# io_shield.net
KiCad netlist of a schematic drawn in EAGLE
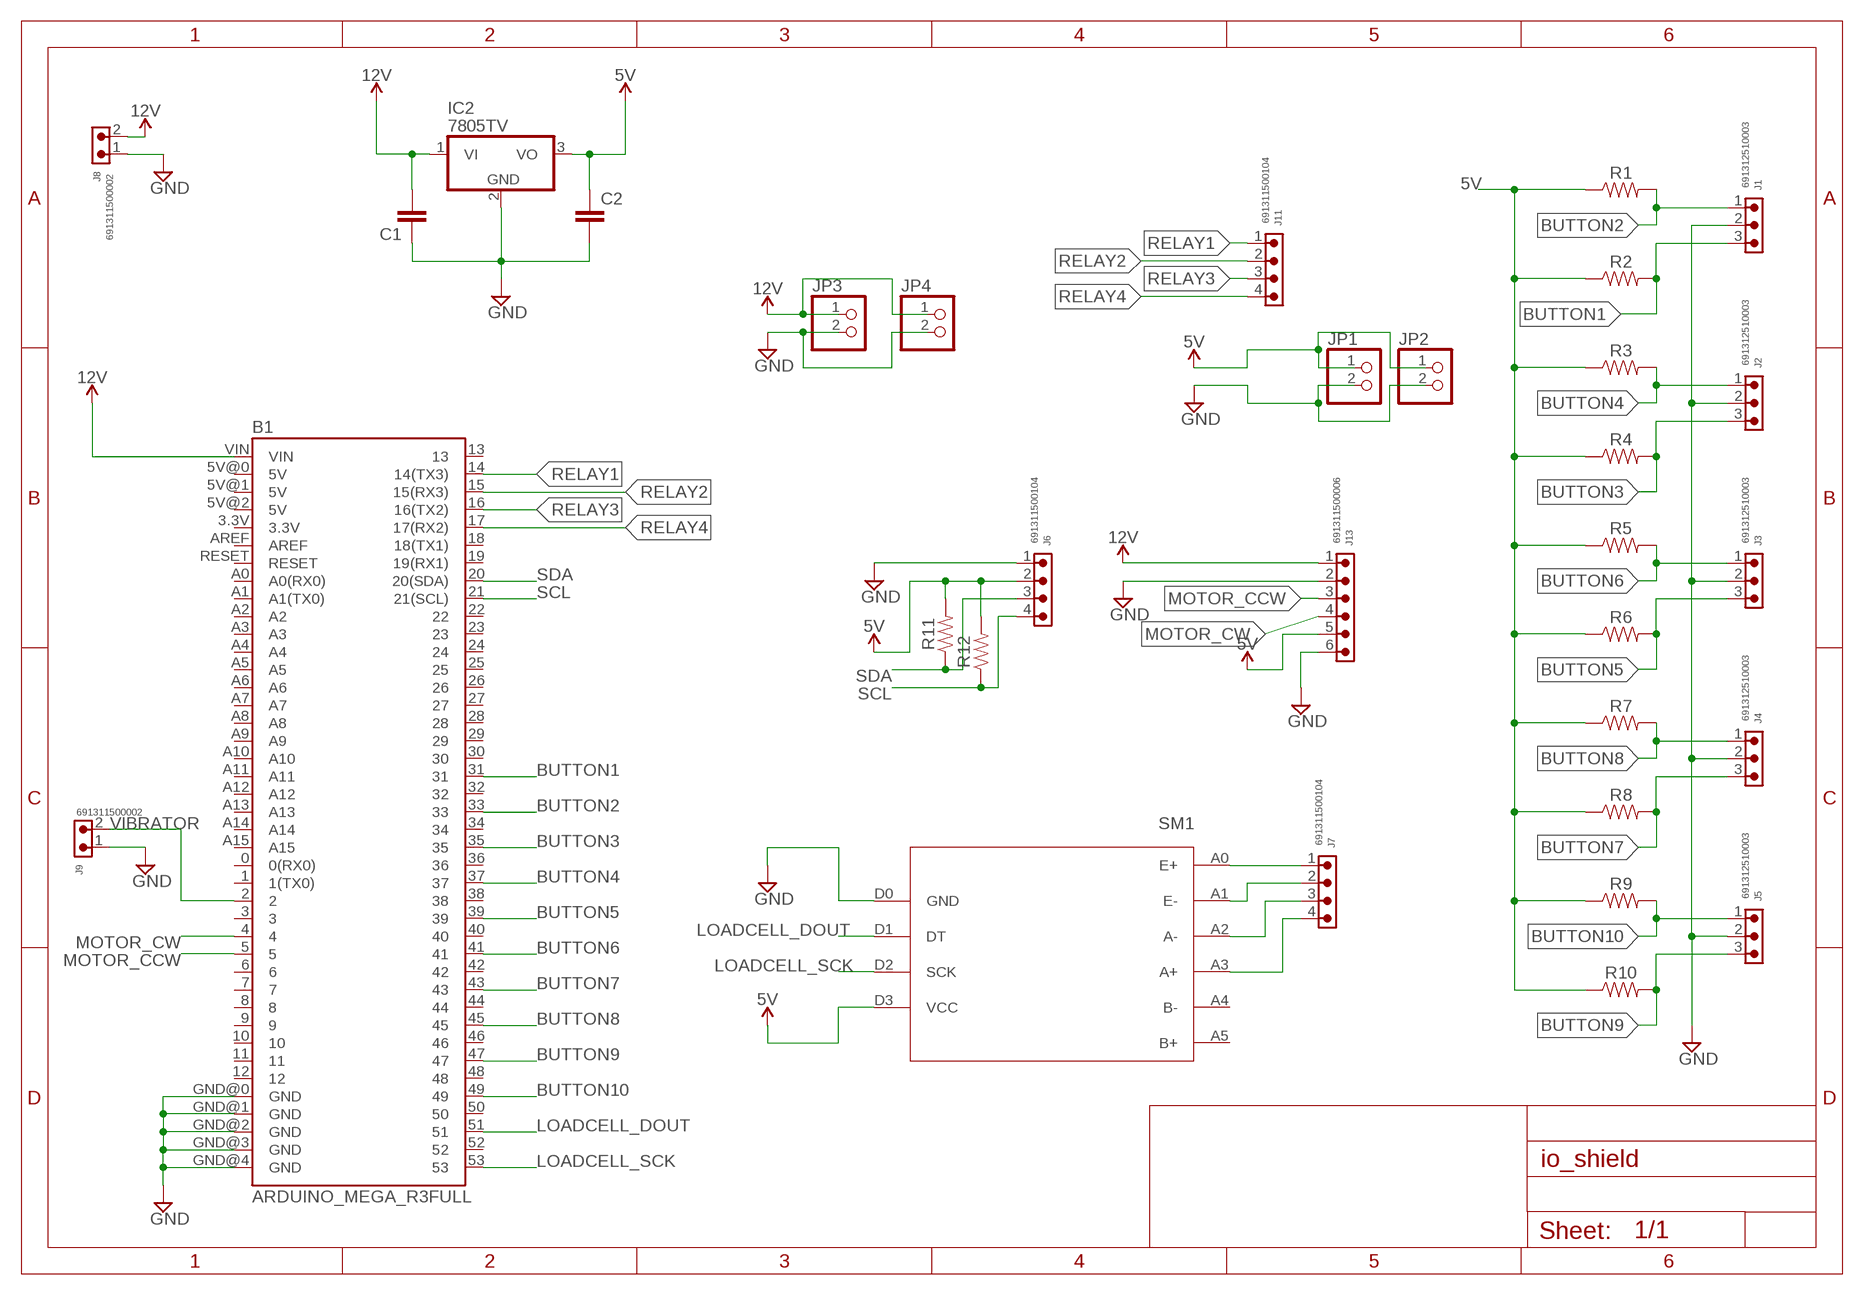
[diagram p0: schematic, sheet 1]

(export (version "E")
  (design (tool "Eeschema 10.0.6"))
  (components
    (comp (ref "B1")
      (value "ARDUINO_MEGA_R3FULL")
      (footprint "eagle-import:ARDUINO_MEGA")
      (libsource (lib "eagle-import") (part "ARDUINO_MEGA_R3FULL"))
    )
    (comp (ref "C1")
      (value "C-EU050-025X075")
      (footprint "eagle-import:C050-025X075")
      (libsource (lib "eagle-import") (part "C-EU050-025X075"))
    )
    (comp (ref "C2")
      (value "C-EU050-025X075")
      (footprint "eagle-import:C050-025X075")
      (libsource (lib "eagle-import") (part "C-EU050-025X075"))
    )
    (comp (ref "IC2")
      (value "7805TV")
      (footprint "eagle-import:TO220V")
      (libsource (lib "eagle-import") (part "78TV05"))
    )
    (comp (ref "J1")
      (value "691312510003")
      (footprint "eagle-import:691312510003")
      (libsource (lib "eagle-import") (part "691312510003"))
    )
    (comp (ref "J2")
      (value "691312510003")
      (footprint "eagle-import:691312510003")
      (libsource (lib "eagle-import") (part "691312510003"))
    )
    (comp (ref "J3")
      (value "691312510003")
      (footprint "eagle-import:691312510003")
      (libsource (lib "eagle-import") (part "691312510003"))
    )
    (comp (ref "J4")
      (value "691312510003")
      (footprint "eagle-import:691312510003")
      (libsource (lib "eagle-import") (part "691312510003"))
    )
    (comp (ref "J5")
      (value "691312510003")
      (footprint "eagle-import:691312510003")
      (libsource (lib "eagle-import") (part "691312510003"))
    )
    (comp (ref "J6")
      (value "691311500104")
      (footprint "eagle-import:691311500104")
      (libsource (lib "eagle-import") (part "691311500104"))
    )
    (comp (ref "J7")
      (value "691311500104")
      (footprint "eagle-import:691311500104")
      (libsource (lib "eagle-import") (part "691311500104"))
    )
    (comp (ref "J8")
      (value "691311500002")
      (footprint "eagle-import:691311500002")
      (libsource (lib "eagle-import") (part "691311500002"))
    )
    (comp (ref "J9")
      (value "691311500002")
      (footprint "eagle-import:691311500002")
      (libsource (lib "eagle-import") (part "691311500002"))
    )
    (comp (ref "J11")
      (value "691311500104")
      (footprint "eagle-import:691311500104")
      (libsource (lib "eagle-import") (part "691311500104"))
    )
    (comp (ref "J13")
      (value "691311500006")
      (footprint "eagle-import:691311500006")
      (libsource (lib "eagle-import") (part "691311500006"))
    )
    (comp (ref "JP1")
      (value "PINHD-1X2")
      (footprint "eagle-import:1X02")
      (libsource (lib "eagle-import") (part "PINHD-1X2"))
    )
    (comp (ref "JP2")
      (value "PINHD-1X2")
      (footprint "eagle-import:1X02")
      (libsource (lib "eagle-import") (part "PINHD-1X2"))
    )
    (comp (ref "JP3")
      (value "PINHD-1X2")
      (footprint "eagle-import:1X02")
      (libsource (lib "eagle-import") (part "PINHD-1X2"))
    )
    (comp (ref "JP4")
      (value "PINHD-1X2")
      (footprint "eagle-import:1X02")
      (libsource (lib "eagle-import") (part "PINHD-1X2"))
    )
    (comp (ref "R1")
      (value "RESISTORAXIAL-0.3")
      (footprint "eagle-import:AXIAL-0.3")
      (libsource (lib "eagle-import") (part "RESISTORAXIAL-0.3"))
    )
    (comp (ref "R2")
      (value "RESISTORAXIAL-0.3")
      (footprint "eagle-import:AXIAL-0.3")
      (libsource (lib "eagle-import") (part "RESISTORAXIAL-0.3"))
    )
    (comp (ref "R3")
      (value "RESISTORAXIAL-0.3")
      (footprint "eagle-import:AXIAL-0.3")
      (libsource (lib "eagle-import") (part "RESISTORAXIAL-0.3"))
    )
    (comp (ref "R4")
      (value "RESISTORAXIAL-0.3")
      (footprint "eagle-import:AXIAL-0.3")
      (libsource (lib "eagle-import") (part "RESISTORAXIAL-0.3"))
    )
    (comp (ref "R5")
      (value "RESISTORAXIAL-0.3")
      (footprint "eagle-import:AXIAL-0.3")
      (libsource (lib "eagle-import") (part "RESISTORAXIAL-0.3"))
    )
    (comp (ref "R6")
      (value "RESISTORAXIAL-0.3")
      (footprint "eagle-import:AXIAL-0.3")
      (libsource (lib "eagle-import") (part "RESISTORAXIAL-0.3"))
    )
    (comp (ref "R7")
      (value "RESISTORAXIAL-0.3")
      (footprint "eagle-import:AXIAL-0.3")
      (libsource (lib "eagle-import") (part "RESISTORAXIAL-0.3"))
    )
    (comp (ref "R8")
      (value "RESISTORAXIAL-0.3")
      (footprint "eagle-import:AXIAL-0.3")
      (libsource (lib "eagle-import") (part "RESISTORAXIAL-0.3"))
    )
    (comp (ref "R9")
      (value "RESISTORAXIAL-0.3")
      (footprint "eagle-import:AXIAL-0.3")
      (libsource (lib "eagle-import") (part "RESISTORAXIAL-0.3"))
    )
    (comp (ref "R10")
      (value "RESISTORAXIAL-0.3")
      (footprint "eagle-import:AXIAL-0.3")
      (libsource (lib "eagle-import") (part "RESISTORAXIAL-0.3"))
    )
    (comp (ref "R11")
      (value "RESISTORAXIAL-0.3")
      (footprint "eagle-import:AXIAL-0.3")
      (libsource (lib "eagle-import") (part "RESISTORAXIAL-0.3"))
    )
    (comp (ref "R12")
      (value "RESISTORAXIAL-0.3")
      (footprint "eagle-import:AXIAL-0.3")
      (libsource (lib "eagle-import") (part "RESISTORAXIAL-0.3"))
    )
    (comp (ref "SM1")
      (value "HX711")
      (footprint "eagle-import:HX711")
      (libsource (lib "eagle-import") (part "HX711"))
    )
  )
  (nets
    (net (code "1") (name "/LOADCELL_DOUT") (class "Default")
      (node (ref "B1") (pin "51") (pinfunction "51_51") (pintype "bidirectional"))
      (node (ref "SM1") (pin "D1") (pinfunction "DT_D1") (pintype "bidirectional"))
    )
    (net (code "2") (name "/LOADCELL_SCK") (class "Default")
      (node (ref "B1") (pin "53") (pinfunction "53_53") (pintype "bidirectional"))
      (node (ref "SM1") (pin "D2") (pinfunction "SCK_D2") (pintype "bidirectional"))
    )
    (net (code "3") (name "/SCL") (class "Default")
      (node (ref "B1") (pin "21") (pinfunction "21(SCL)_21") (pintype "bidirectional"))
      (node (ref "J6") (pin "4") (pinfunction "4_4") (pintype "passive"))
      (node (ref "R12") (pin "P$1") (pinfunction "1_P$1") (pintype "passive"))
    )
    (net (code "4") (name "/SDA") (class "Default")
      (node (ref "B1") (pin "20") (pinfunction "20(SDA)_20") (pintype "bidirectional"))
      (node (ref "J6") (pin "3") (pinfunction "3_3") (pintype "passive"))
      (node (ref "R11") (pin "P$1") (pinfunction "1_P$1") (pintype "passive"))
    )
    (net (code "5") (name "/VIBRATOR") (class "Default")
      (node (ref "B1") (pin "2") (pinfunction "2_2") (pintype "bidirectional"))
      (node (ref "J9") (pin "2") (pinfunction "2_2") (pintype "passive"))
    )
    (net (code "6") (name "5V") (class "Default")
      (node (ref "C2") (pin "1") (pinfunction "1_1") (pintype "passive"))
      (node (ref "IC2") (pin "3") (pinfunction "VO_3") (pintype "passive"))
      (node (ref "J13") (pin "5") (pinfunction "5_5") (pintype "passive"))
      (node (ref "J6") (pin "2") (pinfunction "2_2") (pintype "passive"))
      (node (ref "JP1") (pin "1") (pinfunction "1_1") (pintype "passive"))
      (node (ref "JP2") (pin "1") (pinfunction "1_1") (pintype "passive"))
      (node (ref "R1") (pin "P$1") (pinfunction "1_P$1") (pintype "passive"))
      (node (ref "R10") (pin "P$1") (pinfunction "1_P$1") (pintype "passive"))
      (node (ref "R11") (pin "P$2") (pinfunction "2_P$2") (pintype "passive"))
      (node (ref "R12") (pin "P$2") (pinfunction "2_P$2") (pintype "passive"))
      (node (ref "R2") (pin "P$1") (pinfunction "1_P$1") (pintype "passive"))
      (node (ref "R3") (pin "P$1") (pinfunction "1_P$1") (pintype "passive"))
      (node (ref "R4") (pin "P$1") (pinfunction "1_P$1") (pintype "passive"))
      (node (ref "R5") (pin "P$1") (pinfunction "1_P$1") (pintype "passive"))
      (node (ref "R6") (pin "P$1") (pinfunction "1_P$1") (pintype "passive"))
      (node (ref "R7") (pin "P$1") (pinfunction "1_P$1") (pintype "passive"))
      (node (ref "R8") (pin "P$1") (pinfunction "1_P$1") (pintype "passive"))
      (node (ref "R9") (pin "P$1") (pinfunction "1_P$1") (pintype "passive"))
      (node (ref "SM1") (pin "D3") (pinfunction "VCC_D3") (pintype "bidirectional"))
    )
    (net (code "7") (name "12V") (class "Default")
      (node (ref "B1") (pin "VIN") (pinfunction "VIN_VIN") (pintype "bidirectional"))
      (node (ref "C1") (pin "2") (pinfunction "2_2") (pintype "passive"))
      (node (ref "IC2") (pin "1") (pinfunction "VI_1") (pintype "input"))
      (node (ref "J13") (pin "1") (pinfunction "1_1") (pintype "passive"))
      (node (ref "J8") (pin "2") (pinfunction "2_2") (pintype "passive"))
      (node (ref "JP3") (pin "1") (pinfunction "1_1") (pintype "passive"))
      (node (ref "JP4") (pin "1") (pinfunction "1_1") (pintype "passive"))
    )
    (net (code "8") (name "BUTTON1") (class "Default")
      (node (ref "B1") (pin "31") (pinfunction "31_31") (pintype "bidirectional"))
      (node (ref "J1") (pin "3") (pinfunction "3_3") (pintype "passive"))
      (node (ref "R2") (pin "P$2") (pinfunction "2_P$2") (pintype "passive"))
    )
    (net (code "9") (name "BUTTON2") (class "Default")
      (node (ref "B1") (pin "33") (pinfunction "33_33") (pintype "bidirectional"))
      (node (ref "J1") (pin "1") (pinfunction "1_1") (pintype "passive"))
      (node (ref "R1") (pin "P$2") (pinfunction "2_P$2") (pintype "passive"))
    )
    (net (code "10") (name "BUTTON3") (class "Default")
      (node (ref "B1") (pin "35") (pinfunction "35_35") (pintype "bidirectional"))
      (node (ref "J2") (pin "3") (pinfunction "3_3") (pintype "passive"))
      (node (ref "R4") (pin "P$2") (pinfunction "2_P$2") (pintype "passive"))
    )
    (net (code "11") (name "BUTTON4") (class "Default")
      (node (ref "B1") (pin "37") (pinfunction "37_37") (pintype "bidirectional"))
      (node (ref "J2") (pin "1") (pinfunction "1_1") (pintype "passive"))
      (node (ref "R3") (pin "P$2") (pinfunction "2_P$2") (pintype "passive"))
    )
    (net (code "12") (name "BUTTON5") (class "Default")
      (node (ref "B1") (pin "39") (pinfunction "39_39") (pintype "bidirectional"))
      (node (ref "J3") (pin "3") (pinfunction "3_3") (pintype "passive"))
      (node (ref "R6") (pin "P$2") (pinfunction "2_P$2") (pintype "passive"))
    )
    (net (code "13") (name "BUTTON6") (class "Default")
      (node (ref "B1") (pin "41") (pinfunction "41_41") (pintype "bidirectional"))
      (node (ref "J3") (pin "1") (pinfunction "1_1") (pintype "passive"))
      (node (ref "R5") (pin "P$2") (pinfunction "2_P$2") (pintype "passive"))
    )
    (net (code "14") (name "BUTTON7") (class "Default")
      (node (ref "B1") (pin "43") (pinfunction "43_43") (pintype "bidirectional"))
      (node (ref "J4") (pin "3") (pinfunction "3_3") (pintype "passive"))
      (node (ref "R8") (pin "P$2") (pinfunction "2_P$2") (pintype "passive"))
    )
    (net (code "15") (name "BUTTON8") (class "Default")
      (node (ref "B1") (pin "45") (pinfunction "45_45") (pintype "bidirectional"))
      (node (ref "J4") (pin "1") (pinfunction "1_1") (pintype "passive"))
      (node (ref "R7") (pin "P$2") (pinfunction "2_P$2") (pintype "passive"))
    )
    (net (code "16") (name "BUTTON9") (class "Default")
      (node (ref "B1") (pin "47") (pinfunction "47_47") (pintype "bidirectional"))
      (node (ref "J5") (pin "3") (pinfunction "3_3") (pintype "passive"))
      (node (ref "R10") (pin "P$2") (pinfunction "2_P$2") (pintype "passive"))
    )
    (net (code "17") (name "BUTTON10") (class "Default")
      (node (ref "B1") (pin "49") (pinfunction "49_49") (pintype "bidirectional"))
      (node (ref "J5") (pin "1") (pinfunction "1_1") (pintype "passive"))
      (node (ref "R9") (pin "P$2") (pinfunction "2_P$2") (pintype "passive"))
    )
    (net (code "18") (name "GND") (class "Default")
      (node (ref "B1") (pin "GND@0") (pinfunction "GND_GND@0") (pintype "bidirectional"))
      (node (ref "B1") (pin "GND@1") (pinfunction "GND_GND@1") (pintype "bidirectional"))
      (node (ref "B1") (pin "GND@2") (pinfunction "GND_GND@2") (pintype "bidirectional"))
      (node (ref "B1") (pin "GND@3") (pinfunction "GND_GND@3") (pintype "bidirectional"))
      (node (ref "B1") (pin "GND@4") (pinfunction "GND_GND@4") (pintype "bidirectional"))
      (node (ref "C1") (pin "1") (pinfunction "1_1") (pintype "passive"))
      (node (ref "C2") (pin "2") (pinfunction "2_2") (pintype "passive"))
      (node (ref "IC2") (pin "2") (pinfunction "GND_2") (pintype "passive"))
      (node (ref "J1") (pin "2") (pinfunction "2_2") (pintype "passive"))
      (node (ref "J13") (pin "2") (pinfunction "2_2") (pintype "passive"))
      (node (ref "J13") (pin "6") (pinfunction "6_6") (pintype "passive"))
      (node (ref "J2") (pin "2") (pinfunction "2_2") (pintype "passive"))
      (node (ref "J3") (pin "2") (pinfunction "2_2") (pintype "passive"))
      (node (ref "J4") (pin "2") (pinfunction "2_2") (pintype "passive"))
      (node (ref "J5") (pin "2") (pinfunction "2_2") (pintype "passive"))
      (node (ref "J6") (pin "1") (pinfunction "1_1") (pintype "passive"))
      (node (ref "J8") (pin "1") (pinfunction "1_1") (pintype "passive"))
      (node (ref "J9") (pin "1") (pinfunction "1_1") (pintype "passive"))
      (node (ref "JP1") (pin "2") (pinfunction "2_2") (pintype "passive"))
      (node (ref "JP2") (pin "2") (pinfunction "2_2") (pintype "passive"))
      (node (ref "JP3") (pin "2") (pinfunction "2_2") (pintype "passive"))
      (node (ref "JP4") (pin "2") (pinfunction "2_2") (pintype "passive"))
      (node (ref "SM1") (pin "D0") (pinfunction "GND_D0") (pintype "bidirectional"))
    )
    (net (code "19") (name "MOTOR_CCW") (class "Default")
      (node (ref "B1") (pin "5") (pinfunction "5_5") (pintype "bidirectional"))
      (node (ref "J13") (pin "3") (pinfunction "3_3") (pintype "passive"))
    )
    (net (code "20") (name "MOTOR_CW") (class "Default")
      (node (ref "B1") (pin "4") (pinfunction "4_4") (pintype "bidirectional"))
      (node (ref "J13") (pin "4") (pinfunction "4_4") (pintype "passive"))
    )
    (net (code "21") (name "Net-(SM1-A+)") (class "Default")
      (node (ref "J7") (pin "4") (pinfunction "4_4") (pintype "passive"))
      (node (ref "SM1") (pin "A3") (pinfunction "A+_A3") (pintype "bidirectional"))
    )
    (net (code "22") (name "Net-(SM1-A-)") (class "Default")
      (node (ref "J7") (pin "3") (pinfunction "3_3") (pintype "passive"))
      (node (ref "SM1") (pin "A2") (pinfunction "A-_A2") (pintype "bidirectional"))
    )
    (net (code "23") (name "Net-(SM1-E+)") (class "Default")
      (node (ref "J7") (pin "1") (pinfunction "1_1") (pintype "passive"))
      (node (ref "SM1") (pin "A0") (pinfunction "E+_A0") (pintype "bidirectional"))
    )
    (net (code "24") (name "Net-(SM1-E-)") (class "Default")
      (node (ref "J7") (pin "2") (pinfunction "2_2") (pintype "passive"))
      (node (ref "SM1") (pin "A1") (pinfunction "E-_A1") (pintype "bidirectional"))
    )
    (net (code "25") (name "RELAY1") (class "Default")
      (node (ref "B1") (pin "14") (pinfunction "14(TX3)_14") (pintype "bidirectional"))
      (node (ref "J11") (pin "1") (pinfunction "1_1") (pintype "passive"))
    )
    (net (code "26") (name "RELAY2") (class "Default")
      (node (ref "B1") (pin "15") (pinfunction "15(RX3)_15") (pintype "bidirectional"))
      (node (ref "J11") (pin "2") (pinfunction "2_2") (pintype "passive"))
    )
    (net (code "27") (name "RELAY3") (class "Default")
      (node (ref "B1") (pin "16") (pinfunction "16(TX2)_16") (pintype "bidirectional"))
      (node (ref "J11") (pin "3") (pinfunction "3_3") (pintype "passive"))
    )
    (net (code "28") (name "RELAY4") (class "Default")
      (node (ref "B1") (pin "17") (pinfunction "17(RX2)_17") (pintype "bidirectional"))
      (node (ref "J11") (pin "4") (pinfunction "4_4") (pintype "passive"))
    )
    (net (code "29") (name "unconnected-(B1-0(RX0)-Pad0)") (class "Default")
      (node (ref "B1") (pin "0") (pinfunction "0(RX0)_0") (pintype "bidirectional"))
    )
    (net (code "30") (name "unconnected-(B1-1(TX0)-Pad1)") (class "Default")
      (node (ref "B1") (pin "1") (pinfunction "1(TX0)_1") (pintype "bidirectional"))
    )
    (net (code "31") (name "unconnected-(B1-5V-Pad5V@0)") (class "Default")
      (node (ref "B1") (pin "5V@0") (pinfunction "5V_5V@0") (pintype "bidirectional"))
    )
    (net (code "32") (name "unconnected-(B1-5V-Pad5V@1)") (class "Default")
      (node (ref "B1") (pin "5V@1") (pinfunction "5V_5V@1") (pintype "bidirectional"))
    )
    (net (code "33") (name "unconnected-(B1-5V-Pad5V@2)") (class "Default")
      (node (ref "B1") (pin "5V@2") (pinfunction "5V_5V@2") (pintype "bidirectional"))
    )
    (net (code "34") (name "unconnected-(B1-18(TX1)-Pad18)") (class "Default")
      (node (ref "B1") (pin "18") (pinfunction "18(TX1)_18") (pintype "bidirectional"))
    )
    (net (code "35") (name "unconnected-(B1-19(RX1)-Pad19)") (class "Default")
      (node (ref "B1") (pin "19") (pinfunction "19(RX1)_19") (pintype "bidirectional"))
    )
    (net (code "36") (name "unconnected-(B1-A0(RX0)-PadA0)") (class "Default")
      (node (ref "B1") (pin "A0") (pinfunction "A0(RX0)_A0") (pintype "bidirectional"))
    )
    (net (code "37") (name "unconnected-(B1-A1(TX0)-PadA1)") (class "Default")
      (node (ref "B1") (pin "A1") (pinfunction "A1(TX0)_A1") (pintype "bidirectional"))
    )
    (net (code "38") (name "unconnected-(B1-Pad3)") (class "Default")
      (node (ref "B1") (pin "3") (pinfunction "3_3") (pintype "bidirectional"))
    )
    (net (code "39") (name "unconnected-(B1-Pad3.3V)") (class "Default")
      (node (ref "B1") (pin "3.3V") (pinfunction "3.3V_3.3V") (pintype "bidirectional"))
    )
    (net (code "40") (name "unconnected-(B1-Pad6)") (class "Default")
      (node (ref "B1") (pin "6") (pinfunction "6_6") (pintype "bidirectional"))
    )
    (net (code "41") (name "unconnected-(B1-Pad7)") (class "Default")
      (node (ref "B1") (pin "7") (pinfunction "7_7") (pintype "bidirectional"))
    )
    (net (code "42") (name "unconnected-(B1-Pad8)") (class "Default")
      (node (ref "B1") (pin "8") (pinfunction "8_8") (pintype "bidirectional"))
    )
    (net (code "43") (name "unconnected-(B1-Pad9)") (class "Default")
      (node (ref "B1") (pin "9") (pinfunction "9_9") (pintype "bidirectional"))
    )
    (net (code "44") (name "unconnected-(B1-Pad10)") (class "Default")
      (node (ref "B1") (pin "10") (pinfunction "10_10") (pintype "bidirectional"))
    )
    (net (code "45") (name "unconnected-(B1-Pad11)") (class "Default")
      (node (ref "B1") (pin "11") (pinfunction "11_11") (pintype "bidirectional"))
    )
    (net (code "46") (name "unconnected-(B1-Pad12)") (class "Default")
      (node (ref "B1") (pin "12") (pinfunction "12_12") (pintype "bidirectional"))
    )
    (net (code "47") (name "unconnected-(B1-Pad13)") (class "Default")
      (node (ref "B1") (pin "13") (pinfunction "13_13") (pintype "bidirectional"))
    )
    (net (code "48") (name "unconnected-(B1-Pad22)") (class "Default")
      (node (ref "B1") (pin "22") (pinfunction "22_22") (pintype "bidirectional"))
    )
    (net (code "49") (name "unconnected-(B1-Pad23)") (class "Default")
      (node (ref "B1") (pin "23") (pinfunction "23_23") (pintype "bidirectional"))
    )
    (net (code "50") (name "unconnected-(B1-Pad24)") (class "Default")
      (node (ref "B1") (pin "24") (pinfunction "24_24") (pintype "bidirectional"))
    )
    (net (code "51") (name "unconnected-(B1-Pad25)") (class "Default")
      (node (ref "B1") (pin "25") (pinfunction "25_25") (pintype "bidirectional"))
    )
    (net (code "52") (name "unconnected-(B1-Pad26)") (class "Default")
      (node (ref "B1") (pin "26") (pinfunction "26_26") (pintype "bidirectional"))
    )
    (net (code "53") (name "unconnected-(B1-Pad27)") (class "Default")
      (node (ref "B1") (pin "27") (pinfunction "27_27") (pintype "bidirectional"))
    )
    (net (code "54") (name "unconnected-(B1-Pad28)") (class "Default")
      (node (ref "B1") (pin "28") (pinfunction "28_28") (pintype "bidirectional"))
    )
    (net (code "55") (name "unconnected-(B1-Pad29)") (class "Default")
      (node (ref "B1") (pin "29") (pinfunction "29_29") (pintype "bidirectional"))
    )
    (net (code "56") (name "unconnected-(B1-Pad30)") (class "Default")
      (node (ref "B1") (pin "30") (pinfunction "30_30") (pintype "bidirectional"))
    )
    (net (code "57") (name "unconnected-(B1-Pad32)") (class "Default")
      (node (ref "B1") (pin "32") (pinfunction "32_32") (pintype "bidirectional"))
    )
    (net (code "58") (name "unconnected-(B1-Pad34)") (class "Default")
      (node (ref "B1") (pin "34") (pinfunction "34_34") (pintype "bidirectional"))
    )
    (net (code "59") (name "unconnected-(B1-Pad36)") (class "Default")
      (node (ref "B1") (pin "36") (pinfunction "36_36") (pintype "bidirectional"))
    )
    (net (code "60") (name "unconnected-(B1-Pad38)") (class "Default")
      (node (ref "B1") (pin "38") (pinfunction "38_38") (pintype "bidirectional"))
    )
    (net (code "61") (name "unconnected-(B1-Pad40)") (class "Default")
      (node (ref "B1") (pin "40") (pinfunction "40_40") (pintype "bidirectional"))
    )
    (net (code "62") (name "unconnected-(B1-Pad42)") (class "Default")
      (node (ref "B1") (pin "42") (pinfunction "42_42") (pintype "bidirectional"))
    )
    (net (code "63") (name "unconnected-(B1-Pad44)") (class "Default")
      (node (ref "B1") (pin "44") (pinfunction "44_44") (pintype "bidirectional"))
    )
    (net (code "64") (name "unconnected-(B1-Pad46)") (class "Default")
      (node (ref "B1") (pin "46") (pinfunction "46_46") (pintype "bidirectional"))
    )
    (net (code "65") (name "unconnected-(B1-Pad48)") (class "Default")
      (node (ref "B1") (pin "48") (pinfunction "48_48") (pintype "bidirectional"))
    )
    (net (code "66") (name "unconnected-(B1-Pad50)") (class "Default")
      (node (ref "B1") (pin "50") (pinfunction "50_50") (pintype "bidirectional"))
    )
    (net (code "67") (name "unconnected-(B1-Pad52)") (class "Default")
      (node (ref "B1") (pin "52") (pinfunction "52_52") (pintype "bidirectional"))
    )
    (net (code "68") (name "unconnected-(B1-PadA2)") (class "Default")
      (node (ref "B1") (pin "A2") (pinfunction "A2_A2") (pintype "bidirectional"))
    )
    (net (code "69") (name "unconnected-(B1-PadA3)") (class "Default")
      (node (ref "B1") (pin "A3") (pinfunction "A3_A3") (pintype "bidirectional"))
    )
    (net (code "70") (name "unconnected-(B1-PadA4)") (class "Default")
      (node (ref "B1") (pin "A4") (pinfunction "A4_A4") (pintype "bidirectional"))
    )
    (net (code "71") (name "unconnected-(B1-PadA5)") (class "Default")
      (node (ref "B1") (pin "A5") (pinfunction "A5_A5") (pintype "bidirectional"))
    )
    (net (code "72") (name "unconnected-(B1-PadA6)") (class "Default")
      (node (ref "B1") (pin "A6") (pinfunction "A6_A6") (pintype "bidirectional"))
    )
    (net (code "73") (name "unconnected-(B1-PadA7)") (class "Default")
      (node (ref "B1") (pin "A7") (pinfunction "A7_A7") (pintype "bidirectional"))
    )
    (net (code "74") (name "unconnected-(B1-PadA8)") (class "Default")
      (node (ref "B1") (pin "A8") (pinfunction "A8_A8") (pintype "bidirectional"))
    )
    (net (code "75") (name "unconnected-(B1-PadA9)") (class "Default")
      (node (ref "B1") (pin "A9") (pinfunction "A9_A9") (pintype "bidirectional"))
    )
    (net (code "76") (name "unconnected-(B1-PadA10)") (class "Default")
      (node (ref "B1") (pin "A10") (pinfunction "A10_A10") (pintype "bidirectional"))
    )
    (net (code "77") (name "unconnected-(B1-PadA11)") (class "Default")
      (node (ref "B1") (pin "A11") (pinfunction "A11_A11") (pintype "bidirectional"))
    )
    (net (code "78") (name "unconnected-(B1-PadA12)") (class "Default")
      (node (ref "B1") (pin "A12") (pinfunction "A12_A12") (pintype "bidirectional"))
    )
    (net (code "79") (name "unconnected-(B1-PadA13)") (class "Default")
      (node (ref "B1") (pin "A13") (pinfunction "A13_A13") (pintype "bidirectional"))
    )
    (net (code "80") (name "unconnected-(B1-PadA14)") (class "Default")
      (node (ref "B1") (pin "A14") (pinfunction "A14_A14") (pintype "bidirectional"))
    )
    (net (code "81") (name "unconnected-(B1-PadA15)") (class "Default")
      (node (ref "B1") (pin "A15") (pinfunction "A15_A15") (pintype "bidirectional"))
    )
    (net (code "82") (name "unconnected-(B1-PadAREF)") (class "Default")
      (node (ref "B1") (pin "AREF") (pinfunction "AREF_AREF") (pintype "bidirectional"))
    )
    (net (code "83") (name "unconnected-(B1-PadRESET)") (class "Default")
      (node (ref "B1") (pin "RESET") (pinfunction "RESET_RESET") (pintype "bidirectional"))
    )
    (net (code "84") (name "unconnected-(SM1-B+-PadA5)") (class "Default")
      (node (ref "SM1") (pin "A5") (pinfunction "B+_A5") (pintype "bidirectional"))
    )
    (net (code "85") (name "unconnected-(SM1-B--PadA4)") (class "Default")
      (node (ref "SM1") (pin "A4") (pinfunction "B-_A4") (pintype "bidirectional"))
    )
  )
)
